# mbedXdotShield-V_1_2_0.net
KiCad netlist of a schematic drawn in EAGLE
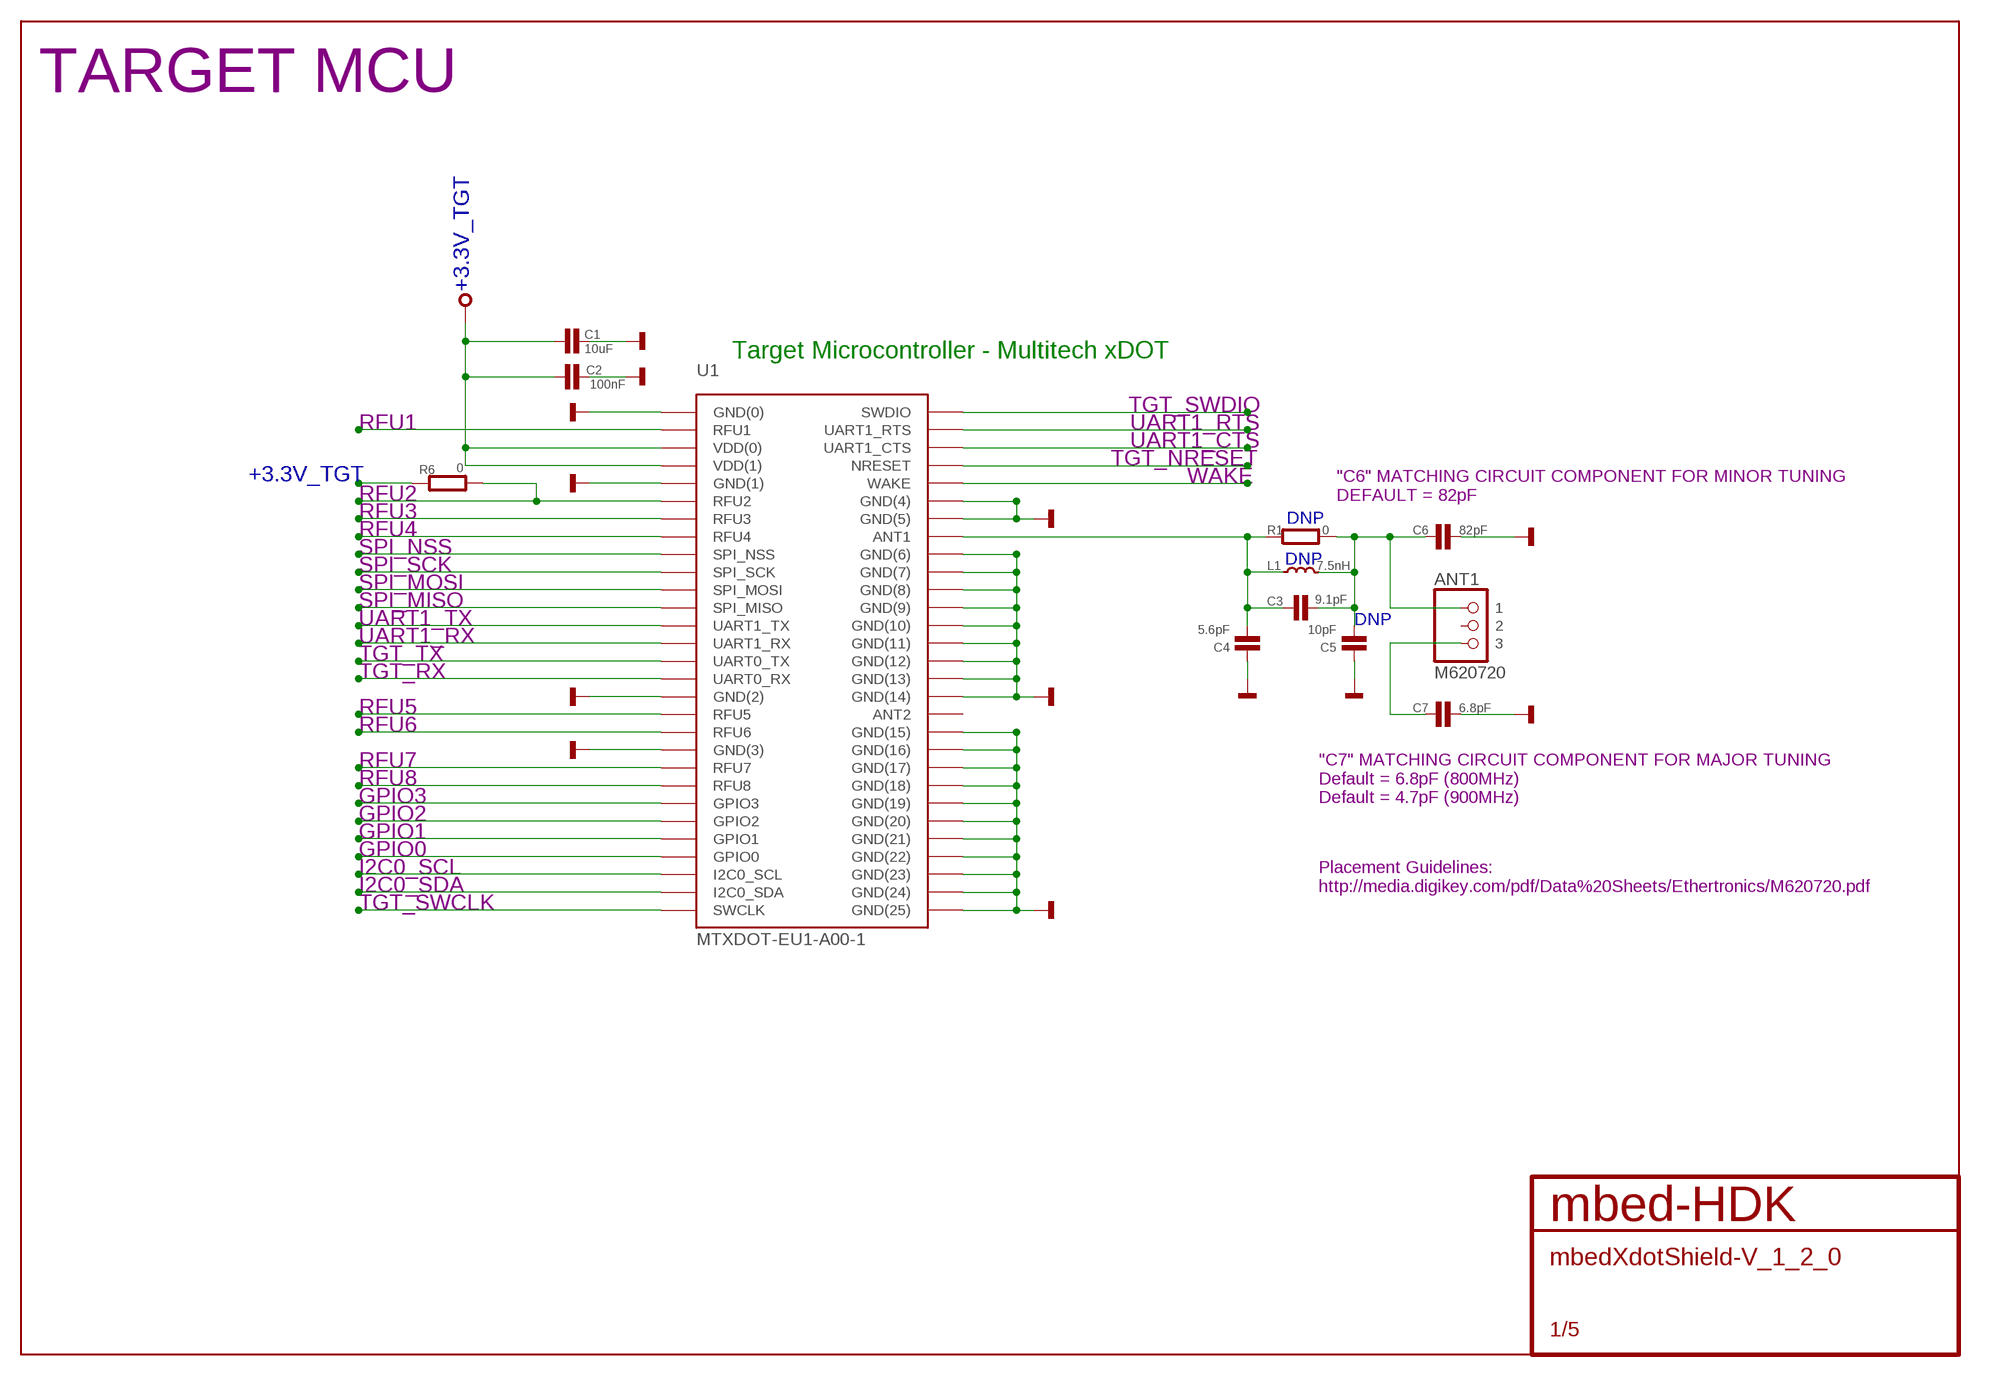
[diagram p0: schematic, sheet 1]
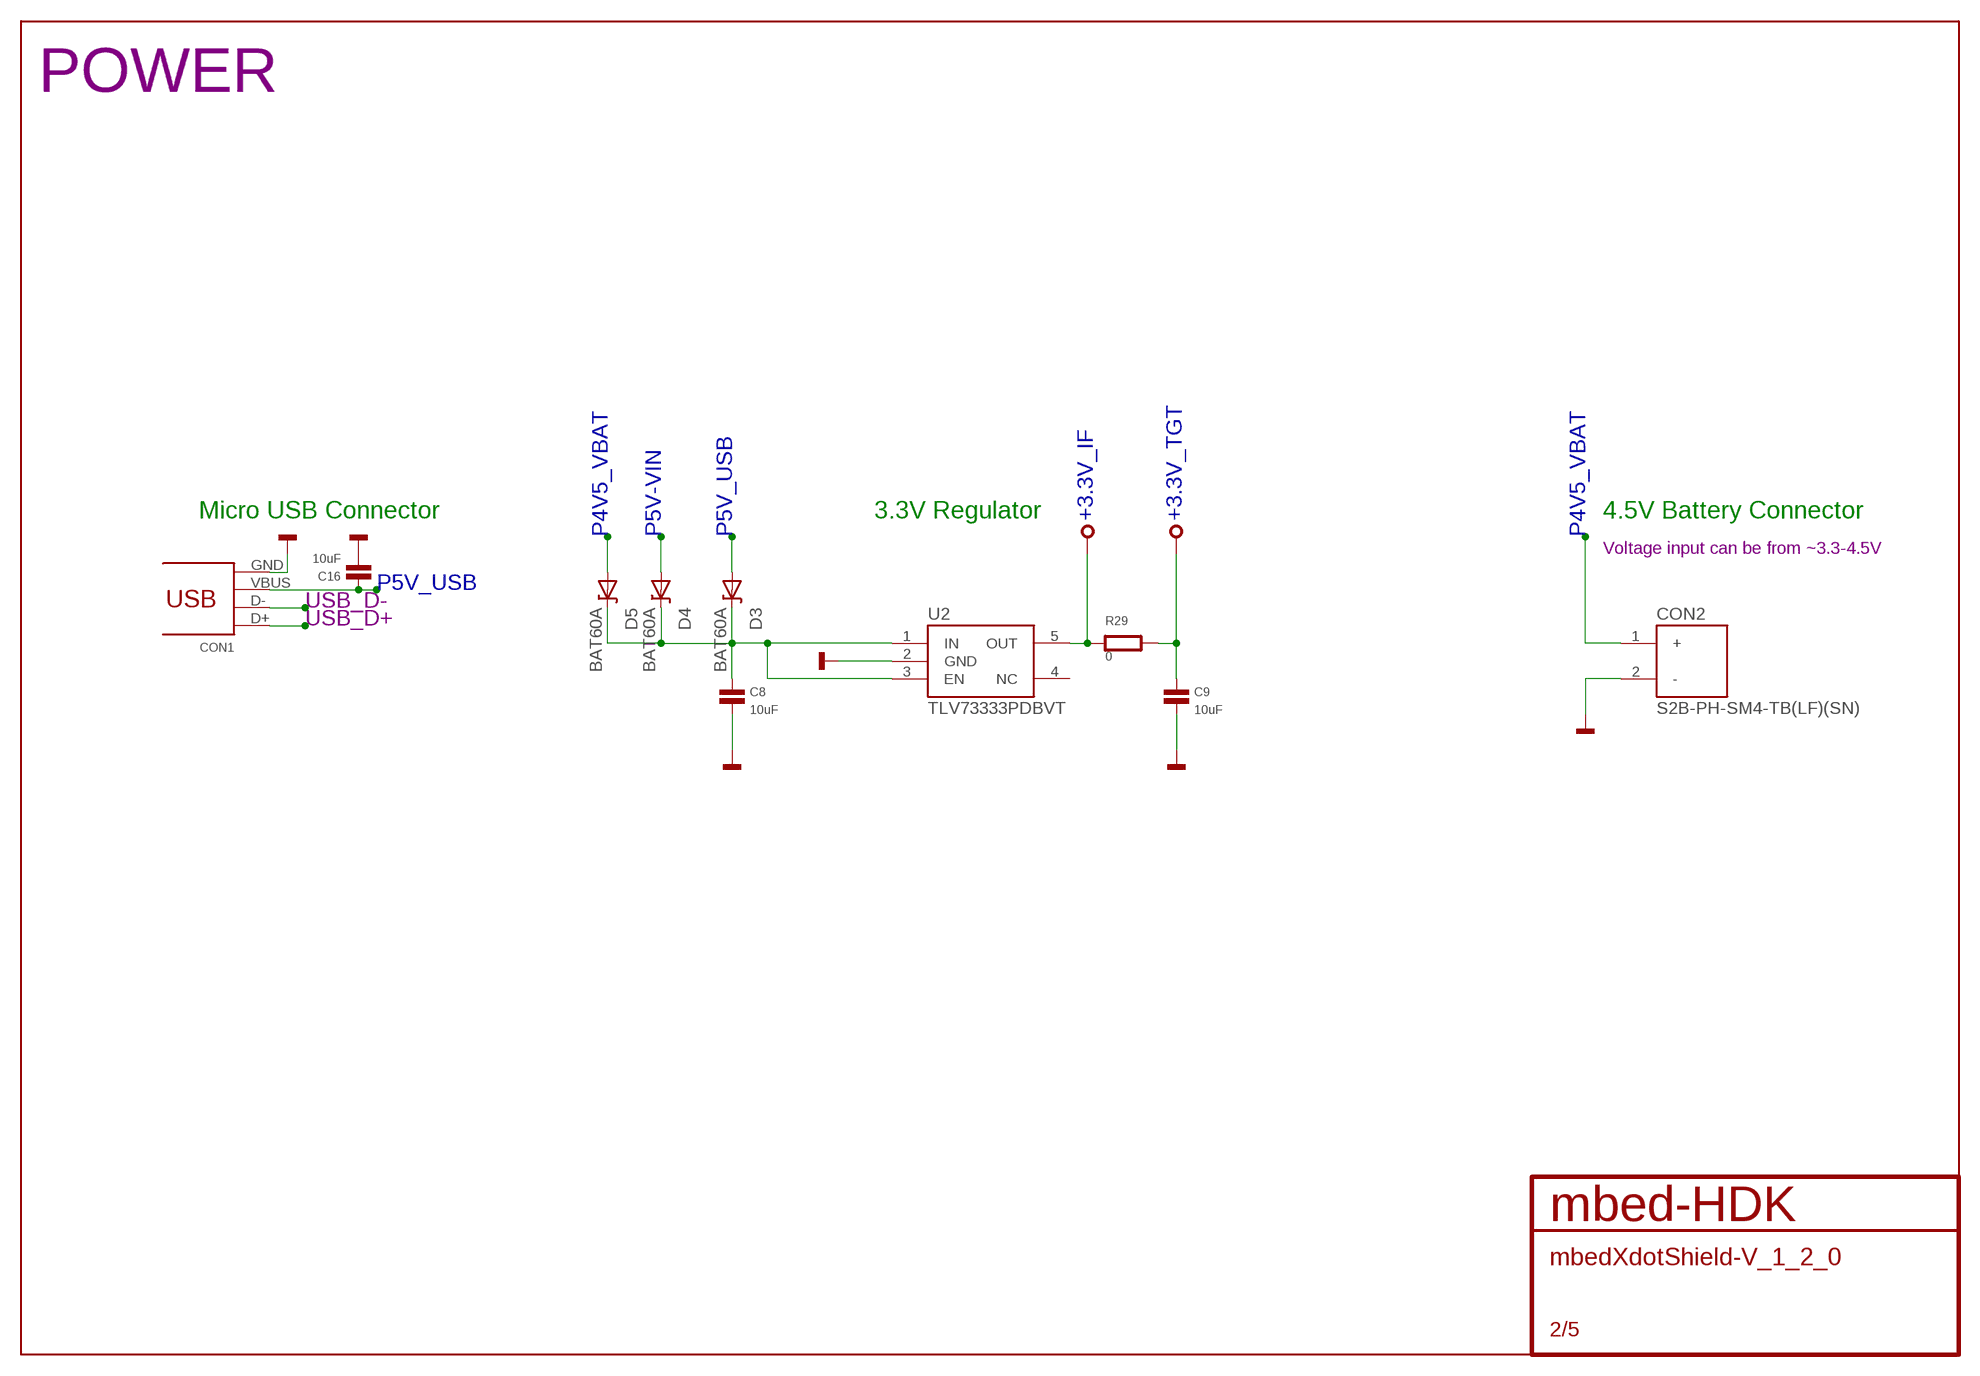
[diagram p1: schematic, sheet 2]
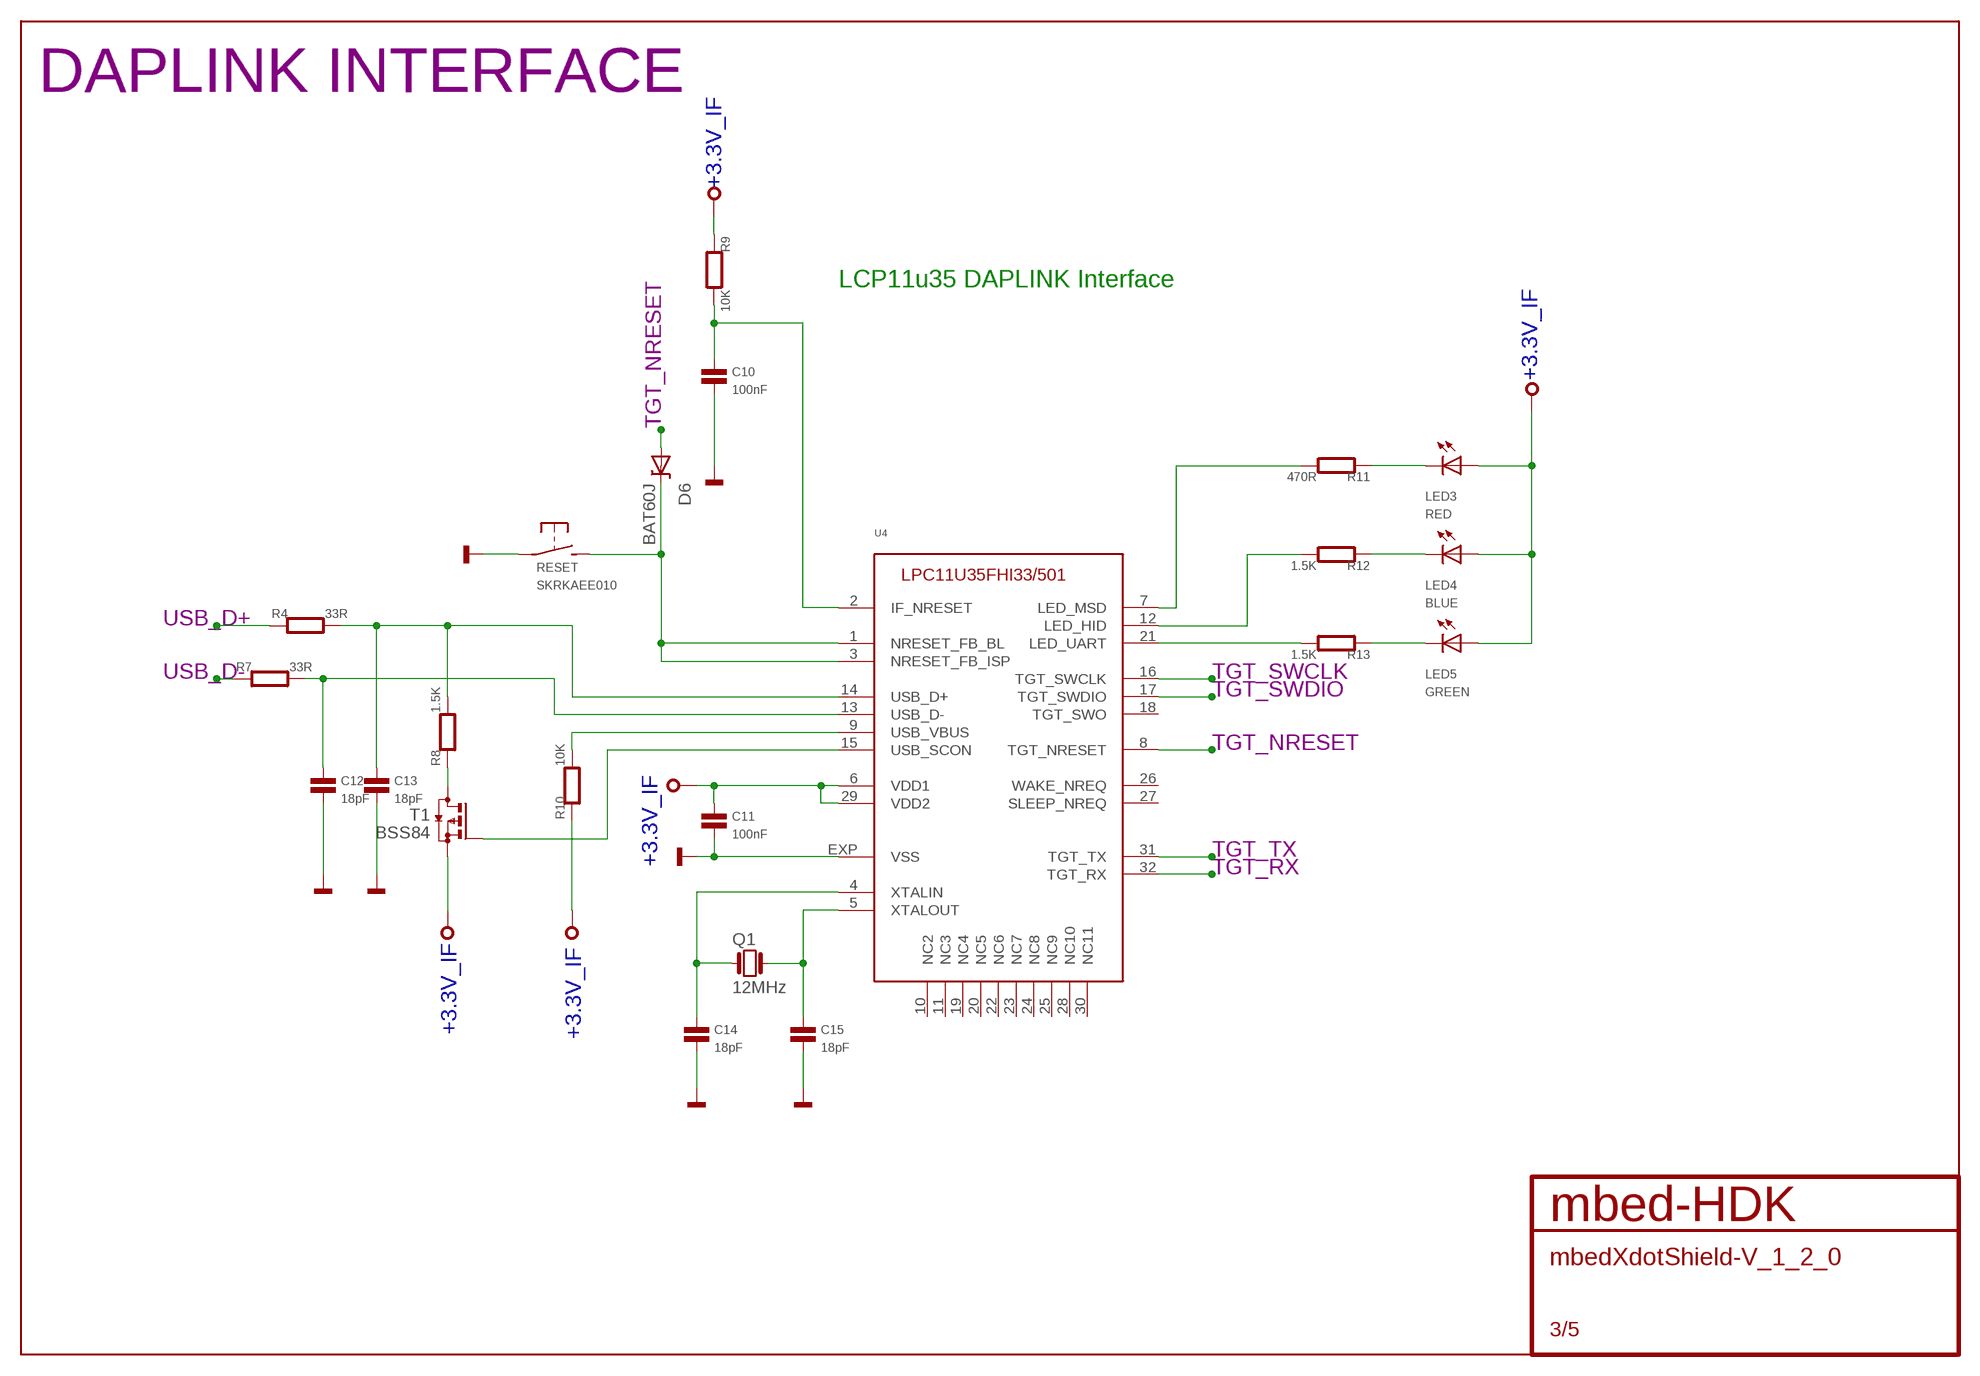
[diagram p2: schematic, sheet 3]
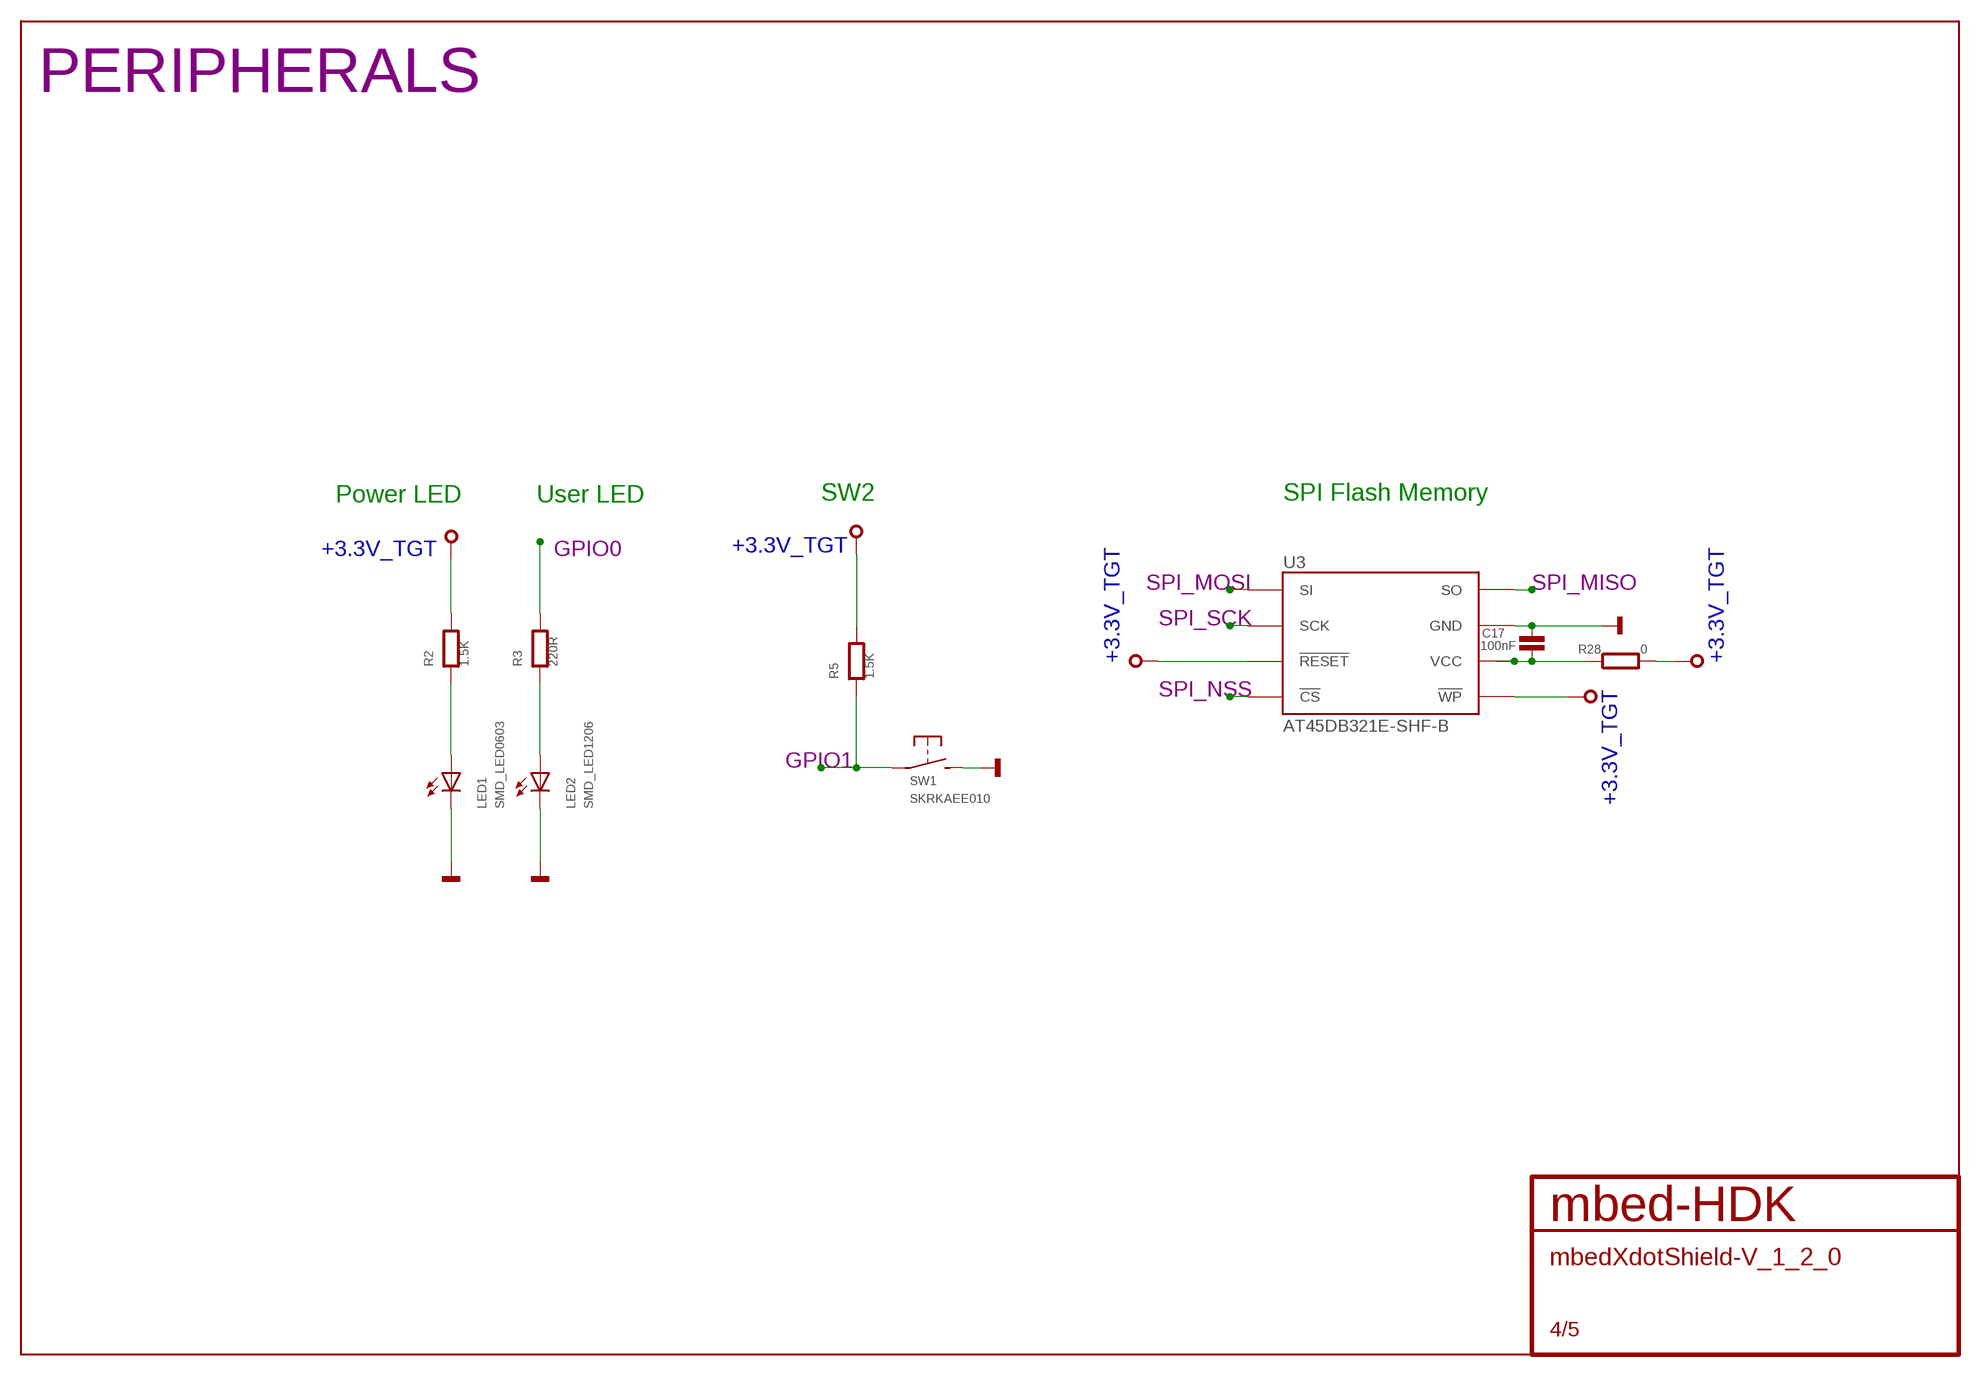
[diagram p3: schematic, sheet 4]
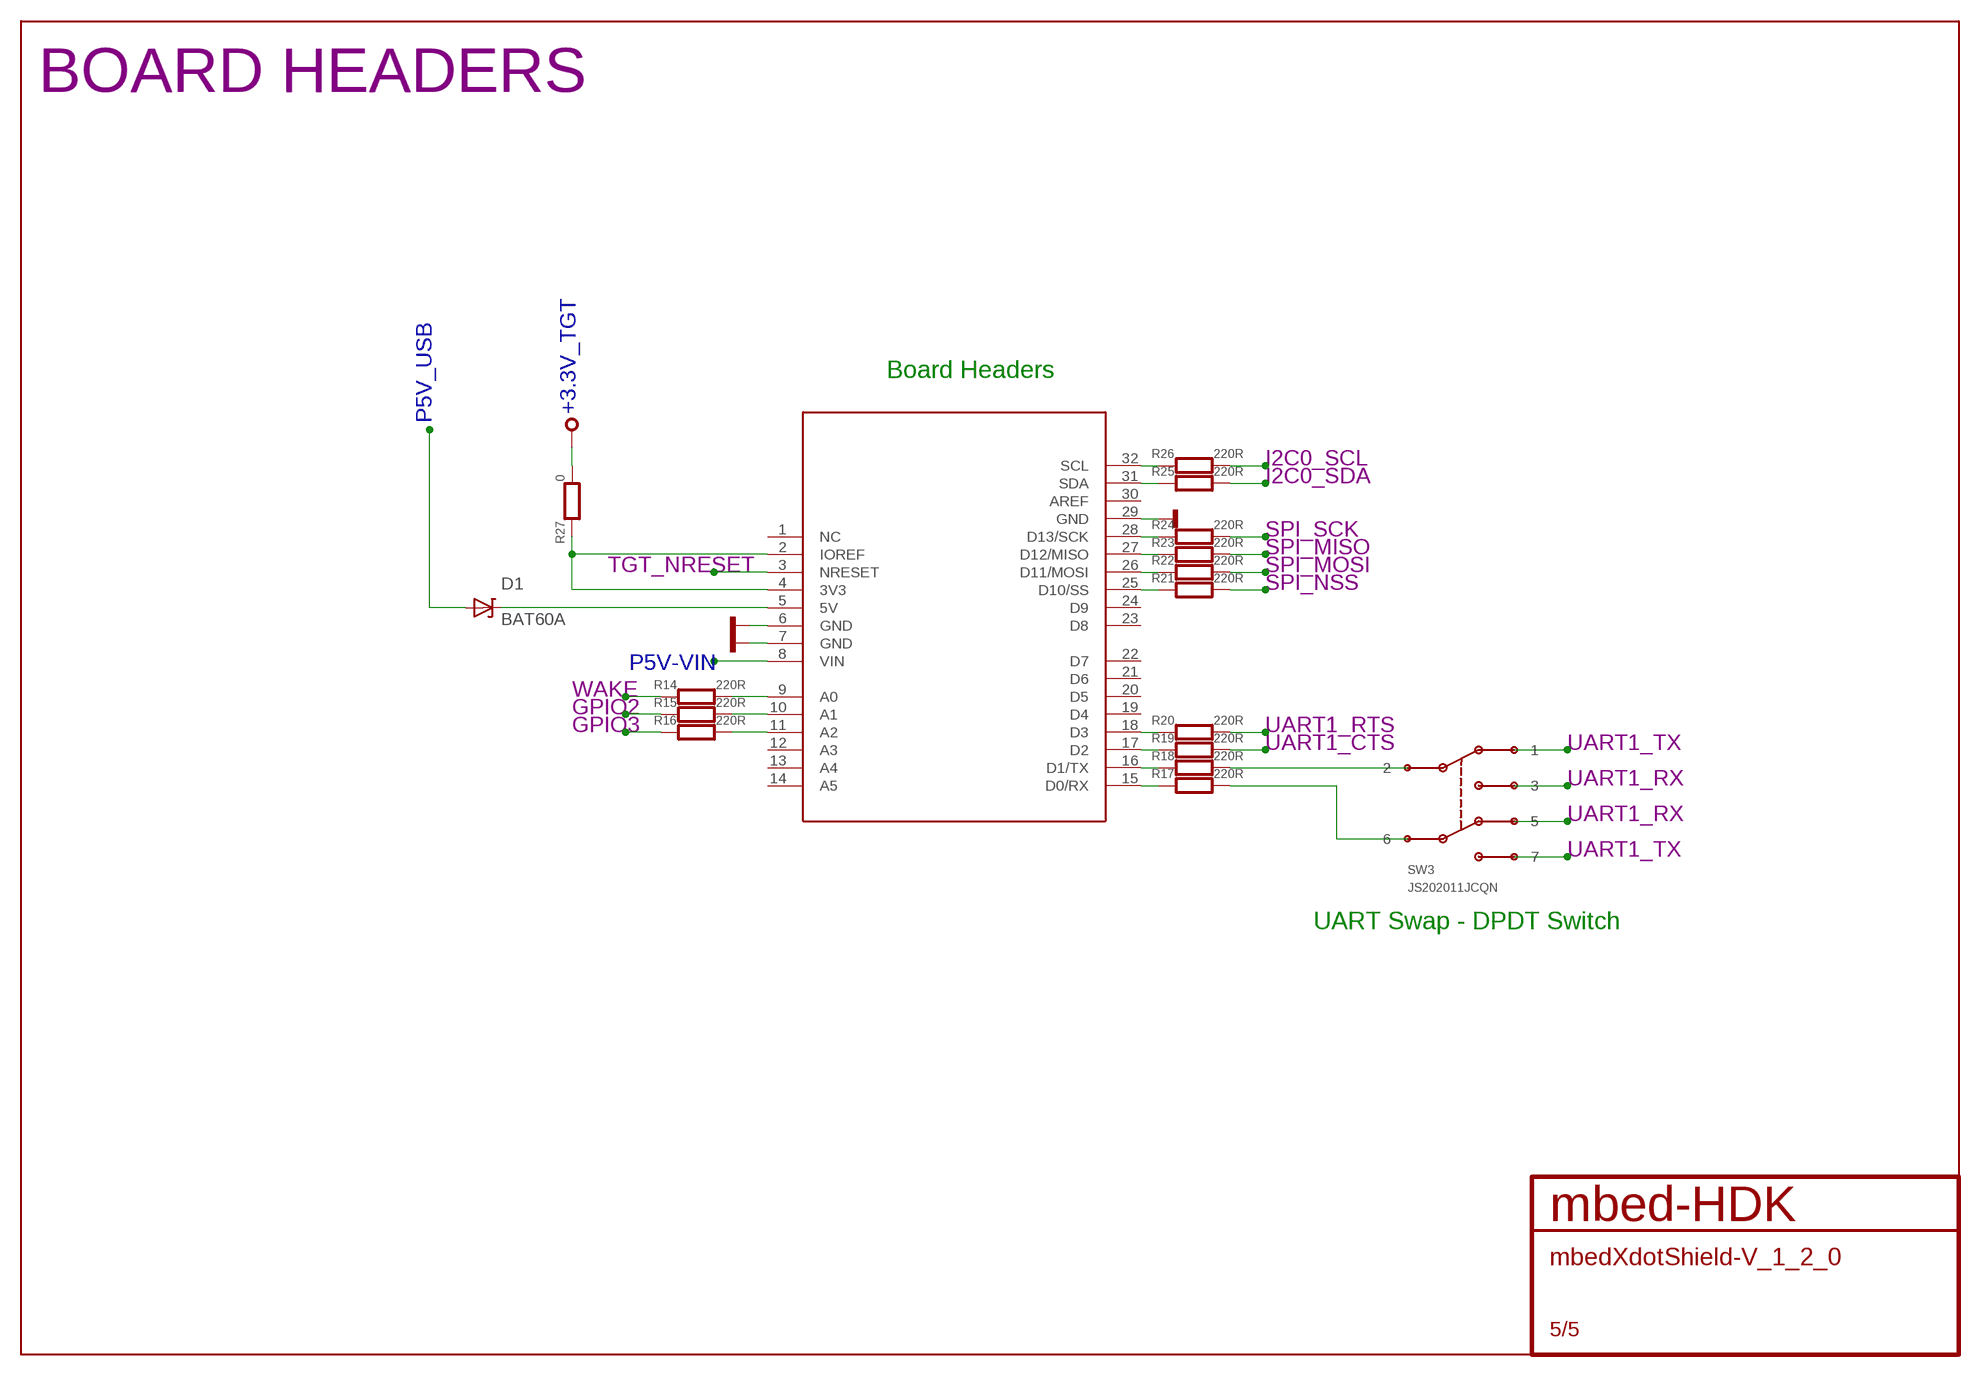
[diagram p4: schematic, sheet 5]

(export (version "E")
  (design (tool "Eeschema 10.0.6"))
  (components
    (comp (ref "BRD1")
      (value "K64F/K22F-SHIELD")
      (footprint "eagle-import:K64F_K22F")
      (libsource (lib "eagle-import") (part "K64F/K22F-SHIELD"))
    )
    (comp (ref "D1")
      (value "BAT60A")
      (footprint "eagle-import:SOD323")
      (fields (field (name "MF") "Infineon"))
      (libsource (lib "eagle-import") (part "BAT60A"))
    )
    (comp (ref "R14")
      (value "220R")
      (footprint "eagle-import:0402")
      (libsource (lib "eagle-import") (part "mbed-HDK-RLCQ_RESISTOR0402"))
    )
    (comp (ref "R15")
      (value "220R")
      (footprint "eagle-import:0402")
      (libsource (lib "eagle-import") (part "mbed-HDK-RLCQ_RESISTOR0402"))
    )
    (comp (ref "R16")
      (value "220R")
      (footprint "eagle-import:0402")
      (libsource (lib "eagle-import") (part "mbed-HDK-RLCQ_RESISTOR0402"))
    )
    (comp (ref "R17")
      (value "220R")
      (footprint "eagle-import:0402")
      (libsource (lib "eagle-import") (part "mbed-HDK-RLCQ_RESISTOR0402"))
    )
    (comp (ref "R18")
      (value "220R")
      (footprint "eagle-import:0402")
      (libsource (lib "eagle-import") (part "mbed-HDK-RLCQ_RESISTOR0402"))
    )
    (comp (ref "R19")
      (value "220R")
      (footprint "eagle-import:0402")
      (libsource (lib "eagle-import") (part "mbed-HDK-RLCQ_RESISTOR0402"))
    )
    (comp (ref "R20")
      (value "220R")
      (footprint "eagle-import:0402")
      (libsource (lib "eagle-import") (part "mbed-HDK-RLCQ_RESISTOR0402"))
    )
    (comp (ref "R21")
      (value "220R")
      (footprint "eagle-import:0402")
      (libsource (lib "eagle-import") (part "mbed-HDK-RLCQ_RESISTOR0402"))
    )
    (comp (ref "R22")
      (value "220R")
      (footprint "eagle-import:0402")
      (libsource (lib "eagle-import") (part "mbed-HDK-RLCQ_RESISTOR0402"))
    )
    (comp (ref "R23")
      (value "220R")
      (footprint "eagle-import:0402")
      (libsource (lib "eagle-import") (part "mbed-HDK-RLCQ_RESISTOR0402"))
    )
    (comp (ref "R24")
      (value "220R")
      (footprint "eagle-import:0402")
      (libsource (lib "eagle-import") (part "mbed-HDK-RLCQ_RESISTOR0402"))
    )
    (comp (ref "R25")
      (value "220R")
      (footprint "eagle-import:0402")
      (libsource (lib "eagle-import") (part "mbed-HDK-RLCQ_RESISTOR0402"))
    )
    (comp (ref "R26")
      (value "220R")
      (footprint "eagle-import:0402")
      (libsource (lib "eagle-import") (part "mbed-HDK-RLCQ_RESISTOR0402"))
    )
    (comp (ref "R27")
      (value "0")
      (footprint "eagle-import:0402")
      (libsource (lib "eagle-import") (part "mbed-HDK-RLCQ_RESISTOR0402"))
    )
    (comp (ref "SW3")
      (value "JS202011JCQN")
      (footprint "eagle-import:JS202011JCQN")
      (fields (field (name "MF") "C&K Components"))
      (libsource (lib "eagle-import") (part "JS202011JCQN"))
    )
    (comp (ref "C17")
      (value "100nF")
      (footprint "eagle-import:0603")
      (libsource (lib "eagle-import") (part "CAPACITOR0603"))
    )
    (comp (ref "LED1")
      (value "SMD_LED0603")
      (footprint "eagle-import:CHIPLED_0603")
      (fields (field (name "MF") "Wurth Electronics Inc"))
      (libsource (lib "eagle-import") (part "SMD_LED0603"))
    )
    (comp (ref "LED2")
      (value "SMD_LED1206")
      (footprint "eagle-import:CHIPLED_1206")
      (fields (field (name "MF") "Wurth Electronics Inc"))
      (libsource (lib "eagle-import") (part "SMD_LED1206"))
    )
    (comp (ref "R2")
      (value "1.5K")
      (footprint "eagle-import:0402")
      (libsource (lib "eagle-import") (part "mbed-HDK-RLCQ_RESISTOR0402"))
    )
    (comp (ref "R3")
      (value "220R")
      (footprint "eagle-import:0402")
      (libsource (lib "eagle-import") (part "mbed-HDK-RLCQ_RESISTOR0402"))
    )
    (comp (ref "R5")
      (value "1.5K")
      (footprint "eagle-import:0402")
      (libsource (lib "eagle-import") (part "mbed-HDK-RLCQ_RESISTOR0402"))
    )
    (comp (ref "R28")
      (value "0")
      (footprint "eagle-import:0402")
      (libsource (lib "eagle-import") (part "mbed-HDK-RLCQ_RESISTOR0402"))
    )
    (comp (ref "SW1")
      (value "SKRKAEE010")
      (footprint "eagle-import:SKRKAEE010")
      (fields (field (name "MF") "ALPS"))
      (libsource (lib "eagle-import") (part "SKRKAEE010"))
    )
    (comp (ref "U3")
      (value "AT45DB321E-SHF-B")
      (footprint "eagle-import:SO8")
      (fields (field (name "MF") "Adesto Technologies"))
      (libsource (lib "eagle-import") (part "AT45DB321E-SHF-B"))
    )
    (comp (ref "ANT1")
      (value "M620720")
      (footprint "eagle-import:M620720")
      (fields (field (name "MF") "Ethertronics"))
      (libsource (lib "eagle-import") (part "M620720"))
    )
    (comp (ref "C1")
      (value "10uF")
      (footprint "eagle-import:0603")
      (libsource (lib "eagle-import") (part "CAPACITOR0603"))
    )
    (comp (ref "C2")
      (value "100nF")
      (footprint "eagle-import:0603")
      (libsource (lib "eagle-import") (part "CAPACITOR0603"))
    )
    (comp (ref "C3")
      (value "9.1pF")
      (footprint "eagle-import:0402")
      (libsource (lib "eagle-import") (part "CAPACITOR0402"))
    )
    (comp (ref "C4")
      (value "5.6pF")
      (footprint "eagle-import:0402")
      (libsource (lib "eagle-import") (part "CAPACITOR0402"))
    )
    (comp (ref "C5")
      (value "10pF")
      (footprint "eagle-import:0402")
      (libsource (lib "eagle-import") (part "CAPACITOR0402"))
    )
    (comp (ref "C6")
      (value "82pF")
      (footprint "eagle-import:0402")
      (libsource (lib "eagle-import") (part "CAPACITOR0402"))
    )
    (comp (ref "C7")
      (value "6.8pF")
      (footprint "eagle-import:0402")
      (libsource (lib "eagle-import") (part "CAPACITOR0402"))
    )
    (comp (ref "L1")
      (value "7.5nH")
      (footprint "eagle-import:0402")
      (libsource (lib "eagle-import") (part "INDUCTOR0402"))
    )
    (comp (ref "R1")
      (value "0")
      (footprint "eagle-import:0402")
      (libsource (lib "eagle-import") (part "mbed-HDK-RLCQ_RESISTOR0402"))
    )
    (comp (ref "R6")
      (value "0")
      (footprint "eagle-import:0402")
      (libsource (lib "eagle-import") (part "mbed-HDK-RLCQ_RESISTOR0402"))
    )
    (comp (ref "U1")
      (value "MTXDOT-EU1-A00-1")
      (footprint "eagle-import:MTXDOT-EU1_NA1-A00-1")
      (fields (field (name "MF") "Multi-Tech Systems Inc."))
      (libsource (lib "eagle-import") (part "MTXDOT-EU1-A00-1"))
    )
    (comp (ref "C10")
      (value "100nF")
      (footprint "eagle-import:0402")
      (libsource (lib "eagle-import") (part "CAPACITOR0402"))
    )
    (comp (ref "C11")
      (value "100nF")
      (footprint "eagle-import:0402")
      (libsource (lib "eagle-import") (part "CAPACITOR0402"))
    )
    (comp (ref "C12")
      (value "18pF")
      (footprint "eagle-import:0402")
      (libsource (lib "eagle-import") (part "CAPACITOR0402"))
    )
    (comp (ref "C13")
      (value "18pF")
      (footprint "eagle-import:0402")
      (libsource (lib "eagle-import") (part "CAPACITOR0402"))
    )
    (comp (ref "C14")
      (value "18pF")
      (footprint "eagle-import:0402")
      (libsource (lib "eagle-import") (part "CAPACITOR0402"))
    )
    (comp (ref "C15")
      (value "18pF")
      (footprint "eagle-import:0402")
      (libsource (lib "eagle-import") (part "CAPACITOR0402"))
    )
    (comp (ref "D6")
      (value "BAT60J")
      (footprint "eagle-import:SOD323")
      (fields (field (name "MF") "STMicroelectronics"))
      (libsource (lib "eagle-import") (part "BAT60J"))
    )
    (comp (ref "LED3")
      (value "RED")
      (footprint "eagle-import:CHIPLED_0603")
      (fields (field (name "MF") "Wurth Electronics Inc"))
      (libsource (lib "eagle-import") (part "SMD_LED0603"))
    )
    (comp (ref "LED4")
      (value "BLUE")
      (footprint "eagle-import:CHIPLED_0603")
      (fields (field (name "MF") "Wurth Electronics Inc"))
      (libsource (lib "eagle-import") (part "SMD_LED0603"))
    )
    (comp (ref "LED5")
      (value "GREEN")
      (footprint "eagle-import:CHIPLED_0603")
      (fields (field (name "MF") "Wurth Electronics Inc"))
      (libsource (lib "eagle-import") (part "SMD_LED0603"))
    )
    (comp (ref "Q1")
      (value "12MHz")
      (footprint "eagle-import:3.2X.2.5")
      (libsource (lib "eagle-import") (part "Q_3.2X2.5"))
    )
    (comp (ref "R4")
      (value "33R")
      (footprint "eagle-import:0402")
      (libsource (lib "eagle-import") (part "mbed-HDK-RLCQ_RESISTOR0402"))
    )
    (comp (ref "R7")
      (value "33R")
      (footprint "eagle-import:0402")
      (libsource (lib "eagle-import") (part "mbed-HDK-RLCQ_RESISTOR0402"))
    )
    (comp (ref "R8")
      (value "1.5K")
      (footprint "eagle-import:0402")
      (libsource (lib "eagle-import") (part "mbed-HDK-RLCQ_RESISTOR0402"))
    )
    (comp (ref "R9")
      (value "10K")
      (footprint "eagle-import:0402")
      (libsource (lib "eagle-import") (part "mbed-HDK-RLCQ_RESISTOR0402"))
    )
    (comp (ref "R10")
      (value "10K")
      (footprint "eagle-import:0402")
      (libsource (lib "eagle-import") (part "mbed-HDK-RLCQ_RESISTOR0402"))
    )
    (comp (ref "R11")
      (value "470R")
      (footprint "eagle-import:0402")
      (libsource (lib "eagle-import") (part "mbed-HDK-RLCQ_RESISTOR0402"))
    )
    (comp (ref "R12")
      (value "1.5K")
      (footprint "eagle-import:0402")
      (libsource (lib "eagle-import") (part "mbed-HDK-RLCQ_RESISTOR0402"))
    )
    (comp (ref "R13")
      (value "1.5K")
      (footprint "eagle-import:0402")
      (libsource (lib "eagle-import") (part "mbed-HDK-RLCQ_RESISTOR0402"))
    )
    (comp (ref "RESET")
      (value "SKRKAEE010")
      (footprint "eagle-import:SKRKAEE010")
      (fields (field (name "MF") "ALPS"))
      (libsource (lib "eagle-import") (part "SKRKAEE010"))
    )
    (comp (ref "T1")
      (value "BSS84")
      (footprint "eagle-import:SOT23-3")
      (fields (field (name "MF") "Fairchild Semiconductor"))
      (libsource (lib "eagle-import") (part "BSS84"))
    )
    (comp (ref "U4")
      (value "IF-LPC11U35")
      (footprint "eagle-import:HVQFN33")
      (libsource (lib "eagle-import") (part "IF-LPC11U35"))
    )
    (comp (ref "C8")
      (value "10uF")
      (footprint "eagle-import:0603")
      (libsource (lib "eagle-import") (part "CAPACITOR0603"))
    )
    (comp (ref "C9")
      (value "10uF")
      (footprint "eagle-import:0603")
      (libsource (lib "eagle-import") (part "CAPACITOR0603"))
    )
    (comp (ref "C16")
      (value "10uF")
      (footprint "eagle-import:0603")
      (libsource (lib "eagle-import") (part "CAPACITOR0603"))
    )
    (comp (ref "CON1")
      (value "47346-0001")
      (footprint "eagle-import:USB-MICRO-B-H")
      (fields (field (name "MF") "MOLEX"))
      (libsource (lib "eagle-import") (part "47346-0001"))
    )
    (comp (ref "CON2")
      (value "S2B-PH-SM4-TB(LF)(SN)")
      (footprint "eagle-import:S2B-PH-SM4-TB(LF)(SN)")
      (fields (field (name "MF") "JST"))
      (libsource (lib "eagle-import") (part "S2B-PH-SM4-TB(LF)(SN)"))
    )
    (comp (ref "D3")
      (value "BAT60A")
      (footprint "eagle-import:SOD323")
      (fields (field (name "MF") "Infineon"))
      (libsource (lib "eagle-import") (part "BAT60A"))
    )
    (comp (ref "D4")
      (value "BAT60A")
      (footprint "eagle-import:SOD323")
      (fields (field (name "MF") "Infineon"))
      (libsource (lib "eagle-import") (part "BAT60A"))
    )
    (comp (ref "D5")
      (value "BAT60A")
      (footprint "eagle-import:SOD323")
      (fields (field (name "MF") "Infineon"))
      (libsource (lib "eagle-import") (part "BAT60A"))
    )
    (comp (ref "R29")
      (value "0")
      (footprint "eagle-import:0805")
      (libsource (lib "eagle-import") (part "RESISTOR0805"))
    )
    (comp (ref "U2")
      (value "TLV73333PDBVT")
      (footprint "eagle-import:SOT23-5")
      (fields (field (name "MF") "Texas Instruments"))
      (libsource (lib "eagle-import") (part "TLV73333PDBVT"))
    )
  )
  (nets
    (net (code "1") (name "+3.3V_IF") (class "Default")
      (node (ref "C11") (pin "1") (pinfunction "P$1_1") (pintype "passive"))
      (node (ref "LED3") (pin "A") (pinfunction "A_A") (pintype "passive"))
      (node (ref "LED4") (pin "A") (pinfunction "A_A") (pintype "passive"))
      (node (ref "LED5") (pin "A") (pinfunction "A_A") (pintype "passive"))
      (node (ref "R10") (pin "1") (pinfunction "P$1_1") (pintype "passive"))
      (node (ref "R29") (pin "1") (pinfunction "P$1_1") (pintype "passive"))
      (node (ref "R9") (pin "1") (pinfunction "P$1_1") (pintype "passive"))
      (node (ref "T1") (pin "2") (pinfunction "S_2") (pintype "passive"))
      (node (ref "U2") (pin "5") (pinfunction "OUT_5") (pintype "bidirectional"))
      (node (ref "U4") (pin "29") (pinfunction "VDD2_29") (pintype "bidirectional"))
      (node (ref "U4") (pin "6") (pinfunction "VDD1_6") (pintype "bidirectional"))
    )
    (net (code "2") (name "+3.3V_TGT") (class "Default")
      (node (ref "C1") (pin "1") (pinfunction "P$1_1") (pintype "passive"))
      (node (ref "C2") (pin "1") (pinfunction "P$1_1") (pintype "passive"))
      (node (ref "C9") (pin "1") (pinfunction "P$1_1") (pintype "passive"))
      (node (ref "R2") (pin "2") (pinfunction "P$2_2") (pintype "passive"))
      (node (ref "R27") (pin "2") (pinfunction "P$2_2") (pintype "passive"))
      (node (ref "R28") (pin "2") (pinfunction "P$2_2") (pintype "passive"))
      (node (ref "R29") (pin "2") (pinfunction "P$2_2") (pintype "passive"))
      (node (ref "R5") (pin "2") (pinfunction "P$2_2") (pintype "passive"))
      (node (ref "R6") (pin "1") (pinfunction "P$1_1") (pintype "passive"))
      (node (ref "U1") (pin "P$3") (pinfunction "VDD(0)_P$3") (pintype "bidirectional"))
      (node (ref "U1") (pin "P$4") (pinfunction "VDD(1)_P$4") (pintype "bidirectional"))
      (node (ref "U3") (pin "3") (pinfunction "~{RESET}_3") (pintype "bidirectional"))
      (node (ref "U3") (pin "5") (pinfunction "~{WP}_5") (pintype "bidirectional"))
    )
    (net (code "3") (name "GND") (class "Default")
      (node (ref "BRD1") (pin "29") (pinfunction "GND_29") (pintype "bidirectional"))
      (node (ref "BRD1") (pin "6") (pinfunction "GND_6") (pintype "bidirectional"))
      (node (ref "BRD1") (pin "7") (pinfunction "GND_7") (pintype "bidirectional"))
      (node (ref "C1") (pin "2") (pinfunction "P$2_2") (pintype "passive"))
      (node (ref "C10") (pin "2") (pinfunction "P$2_2") (pintype "passive"))
      (node (ref "C11") (pin "2") (pinfunction "P$2_2") (pintype "passive"))
      (node (ref "C12") (pin "2") (pinfunction "P$2_2") (pintype "passive"))
      (node (ref "C13") (pin "2") (pinfunction "P$2_2") (pintype "passive"))
      (node (ref "C14") (pin "2") (pinfunction "P$2_2") (pintype "passive"))
      (node (ref "C15") (pin "2") (pinfunction "P$2_2") (pintype "passive"))
      (node (ref "C16") (pin "2") (pinfunction "P$2_2") (pintype "passive"))
      (node (ref "C17") (pin "1") (pinfunction "P$1_1") (pintype "passive"))
      (node (ref "C2") (pin "2") (pinfunction "P$2_2") (pintype "passive"))
      (node (ref "C4") (pin "1") (pinfunction "P$1_1") (pintype "passive"))
      (node (ref "C5") (pin "1") (pinfunction "P$1_1") (pintype "passive"))
      (node (ref "C6") (pin "1") (pinfunction "P$1_1") (pintype "passive"))
      (node (ref "C7") (pin "1") (pinfunction "P$1_1") (pintype "passive"))
      (node (ref "C8") (pin "2") (pinfunction "P$2_2") (pintype "passive"))
      (node (ref "C9") (pin "2") (pinfunction "P$2_2") (pintype "passive"))
      (node (ref "CON1") (pin "GND") (pinfunction "GND_GND") (pintype "bidirectional"))
      (node (ref "CON2") (pin "2") (pinfunction "-_2") (pintype "bidirectional"))
      (node (ref "LED1") (pin "C") (pinfunction "C_C") (pintype "passive"))
      (node (ref "LED2") (pin "C") (pinfunction "C_C") (pintype "passive"))
      (node (ref "RESET") (pin "P$1") (pinfunction "P_P$1") (pintype "passive"))
      (node (ref "SW1") (pin "P$2") (pinfunction "S_P$2") (pintype "passive"))
      (node (ref "U1") (pin "P$1") (pinfunction "GND(0)_P$1") (pintype "bidirectional"))
      (node (ref "U1") (pin "P$17") (pinfunction "GND(2)_P$17") (pintype "bidirectional"))
      (node (ref "U1") (pin "P$20") (pinfunction "GND(3)_P$20") (pintype "bidirectional"))
      (node (ref "U1") (pin "P$35") (pinfunction "GND(4)_P$35") (pintype "bidirectional"))
      (node (ref "U1") (pin "P$36") (pinfunction "GND(5)_P$36") (pintype "bidirectional"))
      (node (ref "U1") (pin "P$38") (pinfunction "GND(6)_P$38") (pintype "bidirectional"))
      (node (ref "U1") (pin "P$39") (pinfunction "GND(7)_P$39") (pintype "bidirectional"))
      (node (ref "U1") (pin "P$40") (pinfunction "GND(8)_P$40") (pintype "bidirectional"))
      (node (ref "U1") (pin "P$41") (pinfunction "GND(9)_P$41") (pintype "bidirectional"))
      (node (ref "U1") (pin "P$42") (pinfunction "GND(10)_P$42") (pintype "bidirectional"))
      (node (ref "U1") (pin "P$43") (pinfunction "GND(11)_P$43") (pintype "bidirectional"))
      (node (ref "U1") (pin "P$44") (pinfunction "GND(12)_P$44") (pintype "bidirectional"))
      (node (ref "U1") (pin "P$45") (pinfunction "GND(13)_P$45") (pintype "bidirectional"))
      (node (ref "U1") (pin "P$46") (pinfunction "GND(14)_P$46") (pintype "bidirectional"))
      (node (ref "U1") (pin "P$48") (pinfunction "GND(15)_P$48") (pintype "bidirectional"))
      (node (ref "U1") (pin "P$49") (pinfunction "GND(16)_P$49") (pintype "bidirectional"))
      (node (ref "U1") (pin "P$5") (pinfunction "GND(1)_P$5") (pintype "bidirectional"))
      (node (ref "U1") (pin "P$50") (pinfunction "GND(17)_P$50") (pintype "bidirectional"))
      (node (ref "U1") (pin "P$51") (pinfunction "GND(18)_P$51") (pintype "bidirectional"))
      (node (ref "U1") (pin "P$52") (pinfunction "GND(19)_P$52") (pintype "bidirectional"))
      (node (ref "U1") (pin "P$53") (pinfunction "GND(20)_P$53") (pintype "bidirectional"))
      (node (ref "U1") (pin "P$54") (pinfunction "GND(21)_P$54") (pintype "bidirectional"))
      (node (ref "U1") (pin "P$55") (pinfunction "GND(22)_P$55") (pintype "bidirectional"))
      (node (ref "U1") (pin "P$56") (pinfunction "GND(23)_P$56") (pintype "bidirectional"))
      (node (ref "U1") (pin "P$57") (pinfunction "GND(24)_P$57") (pintype "bidirectional"))
      (node (ref "U1") (pin "P$58") (pinfunction "GND(25)_P$58") (pintype "bidirectional"))
      (node (ref "U2") (pin "2") (pinfunction "GND_2") (pintype "bidirectional"))
      (node (ref "U3") (pin "7") (pinfunction "GND_7") (pintype "bidirectional"))
      (node (ref "U4") (pin "EXP") (pinfunction "VSS_EXP") (pintype "bidirectional"))
    )
    (net (code "4") (name "GPIO0") (class "Default")
      (node (ref "R3") (pin "2") (pinfunction "P$2_2") (pintype "passive"))
      (node (ref "U1") (pin "P$26") (pinfunction "GPIO0_P$26") (pintype "bidirectional"))
    )
    (net (code "5") (name "GPIO1") (class "Default")
      (node (ref "R5") (pin "1") (pinfunction "P$1_1") (pintype "passive"))
      (node (ref "SW1") (pin "P$1") (pinfunction "P_P$1") (pintype "passive"))
      (node (ref "U1") (pin "P$25") (pinfunction "GPIO1_P$25") (pintype "bidirectional"))
    )
    (net (code "6") (name "GPIO2") (class "Default")
      (node (ref "R15") (pin "1") (pinfunction "P$1_1") (pintype "passive"))
      (node (ref "U1") (pin "P$24") (pinfunction "GPIO2_P$24") (pintype "bidirectional"))
    )
    (net (code "7") (name "GPIO3") (class "Default")
      (node (ref "R16") (pin "1") (pinfunction "P$1_1") (pintype "passive"))
      (node (ref "U1") (pin "P$23") (pinfunction "GPIO3_P$23") (pintype "bidirectional"))
    )
    (net (code "8") (name "I2C0_SCL") (class "Default")
      (node (ref "R26") (pin "2") (pinfunction "P$2_2") (pintype "passive"))
      (node (ref "U1") (pin "P$27") (pinfunction "I2C0_SCL_P$27") (pintype "bidirectional"))
    )
    (net (code "9") (name "I2C0_SDA") (class "Default")
      (node (ref "R25") (pin "2") (pinfunction "P$2_2") (pintype "passive"))
      (node (ref "U1") (pin "P$28") (pinfunction "I2C0_SDA_P$28") (pintype "bidirectional"))
    )
    (net (code "10") (name "Net-(ANT1-1)") (class "Default")
      (node (ref "ANT1") (pin "P$1") (pinfunction "1_P$1") (pintype "passive"))
      (node (ref "C3") (pin "2") (pinfunction "P$2_2") (pintype "passive"))
      (node (ref "C5") (pin "2") (pinfunction "P$2_2") (pintype "passive"))
      (node (ref "C6") (pin "2") (pinfunction "P$2_2") (pintype "passive"))
      (node (ref "L1") (pin "2") (pinfunction "P$2_2") (pintype "bidirectional"))
      (node (ref "R1") (pin "2") (pinfunction "P$2_2") (pintype "passive"))
    )
    (net (code "11") (name "Net-(ANT1-3)") (class "Default")
      (node (ref "ANT1") (pin "P$3") (pinfunction "3_P$3") (pintype "passive"))
      (node (ref "C7") (pin "2") (pinfunction "P$2_2") (pintype "passive"))
    )
    (net (code "12") (name "Net-(BRD1-3V3)") (class "Default")
      (node (ref "BRD1") (pin "2") (pinfunction "IOREF_2") (pintype "bidirectional"))
      (node (ref "BRD1") (pin "4") (pinfunction "3V3_4") (pintype "bidirectional"))
      (node (ref "R27") (pin "1") (pinfunction "P$1_1") (pintype "passive"))
    )
    (net (code "13") (name "Net-(BRD1-5V)") (class "Default")
      (node (ref "BRD1") (pin "5") (pinfunction "5V_5") (pintype "bidirectional"))
      (node (ref "D1") (pin "K") (pinfunction "K_K") (pintype "passive"))
    )
    (net (code "14") (name "Net-(BRD1-A0)") (class "Default")
      (node (ref "BRD1") (pin "9") (pinfunction "A0_9") (pintype "bidirectional"))
      (node (ref "R14") (pin "2") (pinfunction "P$2_2") (pintype "passive"))
    )
    (net (code "15") (name "Net-(BRD1-A1)") (class "Default")
      (node (ref "BRD1") (pin "10") (pinfunction "A1_10") (pintype "bidirectional"))
      (node (ref "R15") (pin "2") (pinfunction "P$2_2") (pintype "passive"))
    )
    (net (code "16") (name "Net-(BRD1-A2)") (class "Default")
      (node (ref "BRD1") (pin "11") (pinfunction "A2_11") (pintype "bidirectional"))
      (node (ref "R16") (pin "2") (pinfunction "P$2_2") (pintype "passive"))
    )
    (net (code "17") (name "Net-(BRD1-D0{slash}RX)") (class "Default")
      (node (ref "BRD1") (pin "15") (pinfunction "D0/RX_15") (pintype "bidirectional"))
      (node (ref "R17") (pin "1") (pinfunction "P$1_1") (pintype "passive"))
    )
    (net (code "18") (name "Net-(BRD1-D1{slash}TX)") (class "Default")
      (node (ref "BRD1") (pin "16") (pinfunction "D1/TX_16") (pintype "bidirectional"))
      (node (ref "R18") (pin "1") (pinfunction "P$1_1") (pintype "passive"))
    )
    (net (code "19") (name "Net-(BRD1-D2)") (class "Default")
      (node (ref "BRD1") (pin "17") (pinfunction "D2_17") (pintype "bidirectional"))
      (node (ref "R19") (pin "1") (pinfunction "P$1_1") (pintype "passive"))
    )
    (net (code "20") (name "Net-(BRD1-D3)") (class "Default")
      (node (ref "BRD1") (pin "18") (pinfunction "D3_18") (pintype "bidirectional"))
      (node (ref "R20") (pin "1") (pinfunction "P$1_1") (pintype "passive"))
    )
    (net (code "21") (name "Net-(BRD1-D10{slash}SS)") (class "Default")
      (node (ref "BRD1") (pin "25") (pinfunction "D10/SS_25") (pintype "bidirectional"))
      (node (ref "R21") (pin "1") (pinfunction "P$1_1") (pintype "passive"))
    )
    (net (code "22") (name "Net-(BRD1-D11{slash}MOSI)") (class "Default")
      (node (ref "BRD1") (pin "26") (pinfunction "D11/MOSI_26") (pintype "bidirectional"))
      (node (ref "R22") (pin "1") (pinfunction "P$1_1") (pintype "passive"))
    )
    (net (code "23") (name "Net-(BRD1-D12{slash}MISO)") (class "Default")
      (node (ref "BRD1") (pin "27") (pinfunction "D12/MISO_27") (pintype "bidirectional"))
      (node (ref "R23") (pin "1") (pinfunction "P$1_1") (pintype "passive"))
    )
    (net (code "24") (name "Net-(BRD1-D13{slash}SCK)") (class "Default")
      (node (ref "BRD1") (pin "28") (pinfunction "D13/SCK_28") (pintype "bidirectional"))
      (node (ref "R24") (pin "1") (pinfunction "P$1_1") (pintype "passive"))
    )
    (net (code "25") (name "Net-(BRD1-SCL)") (class "Default")
      (node (ref "BRD1") (pin "32") (pinfunction "SCL_32") (pintype "bidirectional"))
      (node (ref "R26") (pin "1") (pinfunction "P$1_1") (pintype "passive"))
    )
    (net (code "26") (name "Net-(BRD1-SDA)") (class "Default")
      (node (ref "BRD1") (pin "31") (pinfunction "SDA_31") (pintype "bidirectional"))
      (node (ref "R25") (pin "1") (pinfunction "P$1_1") (pintype "passive"))
    )
    (net (code "27") (name "Net-(C3-P$1)") (class "Default")
      (node (ref "C3") (pin "1") (pinfunction "P$1_1") (pintype "passive"))
      (node (ref "C4") (pin "2") (pinfunction "P$2_2") (pintype "passive"))
      (node (ref "L1") (pin "1") (pinfunction "P$1_1") (pintype "bidirectional"))
      (node (ref "R1") (pin "1") (pinfunction "P$1_1") (pintype "passive"))
      (node (ref "U1") (pin "P$37") (pinfunction "ANT1_P$37") (pintype "bidirectional"))
    )
    (net (code "28") (name "Net-(C8-P$1)") (class "Default")
      (node (ref "C8") (pin "1") (pinfunction "P$1_1") (pintype "passive"))
      (node (ref "D3") (pin "K") (pinfunction "K_K") (pintype "passive"))
      (node (ref "D4") (pin "K") (pinfunction "K_K") (pintype "passive"))
      (node (ref "D5") (pin "K") (pinfunction "K_K") (pintype "passive"))
      (node (ref "U2") (pin "1") (pinfunction "IN_1") (pintype "bidirectional"))
      (node (ref "U2") (pin "3") (pinfunction "EN_3") (pintype "bidirectional"))
    )
    (net (code "29") (name "Net-(C10-P$1)") (class "Default")
      (node (ref "C10") (pin "1") (pinfunction "P$1_1") (pintype "passive"))
      (node (ref "R9") (pin "2") (pinfunction "P$2_2") (pintype "passive"))
      (node (ref "U4") (pin "2") (pinfunction "IF_NRESET_2") (pintype "bidirectional"))
    )
    (net (code "30") (name "Net-(C12-P$1)") (class "Default")
      (node (ref "C12") (pin "1") (pinfunction "P$1_1") (pintype "passive"))
      (node (ref "R7") (pin "2") (pinfunction "P$2_2") (pintype "passive"))
      (node (ref "U4") (pin "13") (pinfunction "USB_D-_13") (pintype "bidirectional"))
    )
    (net (code "31") (name "Net-(C13-P$1)") (class "Default")
      (node (ref "C13") (pin "1") (pinfunction "P$1_1") (pintype "passive"))
      (node (ref "R4") (pin "2") (pinfunction "P$2_2") (pintype "passive"))
      (node (ref "R8") (pin "2") (pinfunction "P$2_2") (pintype "passive"))
      (node (ref "U4") (pin "14") (pinfunction "USB_D+_14") (pintype "bidirectional"))
    )
    (net (code "32") (name "Net-(C14-P$1)") (class "Default")
      (node (ref "C14") (pin "1") (pinfunction "P$1_1") (pintype "passive"))
      (node (ref "Q1") (pin "P$1") (pinfunction "1_P$1") (pintype "passive"))
      (node (ref "U4") (pin "4") (pinfunction "XTALIN_4") (pintype "bidirectional"))
    )
    (net (code "33") (name "Net-(C15-P$1)") (class "Default")
      (node (ref "C15") (pin "1") (pinfunction "P$1_1") (pintype "passive"))
      (node (ref "Q1") (pin "P$3") (pinfunction "2_P$3") (pintype "passive"))
      (node (ref "U4") (pin "5") (pinfunction "XTALOUT_5") (pintype "bidirectional"))
    )
    (net (code "34") (name "Net-(C17-P$2)") (class "Default")
      (node (ref "C17") (pin "2") (pinfunction "P$2_2") (pintype "passive"))
      (node (ref "R28") (pin "1") (pinfunction "P$1_1") (pintype "passive"))
      (node (ref "U3") (pin "6") (pinfunction "VCC_6") (pintype "bidirectional"))
    )
    (net (code "35") (name "Net-(R2-P$1)") (class "Default")
      (node (ref "LED1") (pin "A") (pinfunction "A_A") (pintype "passive"))
      (node (ref "R2") (pin "1") (pinfunction "P$1_1") (pintype "passive"))
    )
    (net (code "36") (name "Net-(R3-P$1)") (class "Default")
      (node (ref "LED2") (pin "A") (pinfunction "A_A") (pintype "passive"))
      (node (ref "R3") (pin "1") (pinfunction "P$1_1") (pintype "passive"))
    )
    (net (code "37") (name "Net-(R8-P$1)") (class "Default")
      (node (ref "R8") (pin "1") (pinfunction "P$1_1") (pintype "passive"))
      (node (ref "T1") (pin "3") (pinfunction "D_3") (pintype "passive"))
    )
    (net (code "38") (name "Net-(R10-P$2)") (class "Default")
      (node (ref "R10") (pin "2") (pinfunction "P$2_2") (pintype "passive"))
      (node (ref "U4") (pin "9") (pinfunction "USB_VBUS_9") (pintype "bidirectional"))
    )
    (net (code "39") (name "Net-(R11-P$1)") (class "Default")
      (node (ref "LED3") (pin "C") (pinfunction "C_C") (pintype "passive"))
      (node (ref "R11") (pin "1") (pinfunction "P$1_1") (pintype "passive"))
    )
    (net (code "40") (name "Net-(R11-P$2)") (class "Default")
      (node (ref "R11") (pin "2") (pinfunction "P$2_2") (pintype "passive"))
      (node (ref "U4") (pin "7") (pinfunction "LED_MSD_7") (pintype "bidirectional"))
    )
    (net (code "41") (name "Net-(R12-P$1)") (class "Default")
      (node (ref "LED4") (pin "C") (pinfunction "C_C") (pintype "passive"))
      (node (ref "R12") (pin "1") (pinfunction "P$1_1") (pintype "passive"))
    )
    (net (code "42") (name "Net-(R12-P$2)") (class "Default")
      (node (ref "R12") (pin "2") (pinfunction "P$2_2") (pintype "passive"))
      (node (ref "U4") (pin "12") (pinfunction "LED_HID_12") (pintype "bidirectional"))
    )
    (net (code "43") (name "Net-(R13-P$1)") (class "Default")
      (node (ref "LED5") (pin "C") (pinfunction "C_C") (pintype "passive"))
      (node (ref "R13") (pin "1") (pinfunction "P$1_1") (pintype "passive"))
    )
    (net (code "44") (name "Net-(R13-P$2)") (class "Default")
      (node (ref "R13") (pin "2") (pinfunction "P$2_2") (pintype "passive"))
      (node (ref "U4") (pin "21") (pinfunction "LED_UART_21") (pintype "bidirectional"))
    )
    (net (code "45") (name "Net-(R17-P$2)") (class "Default")
      (node (ref "R17") (pin "2") (pinfunction "P$2_2") (pintype "passive"))
      (node (ref "SW3") (pin "6") (pinfunction "6_6") (pintype "bidirectional"))
    )
    (net (code "46") (name "Net-(R18-P$2)") (class "Default")
      (node (ref "R18") (pin "2") (pinfunction "P$2_2") (pintype "passive"))
      (node (ref "SW3") (pin "2") (pinfunction "2_2") (pintype "bidirectional"))
    )
    (net (code "47") (name "Net-(RESET-S)") (class "Default")
      (node (ref "D6") (pin "K") (pinfunction "K_K") (pintype "passive"))
      (node (ref "RESET") (pin "P$2") (pinfunction "S_P$2") (pintype "passive"))
      (node (ref "U4") (pin "1") (pinfunction "NRESET_FB_BL_1") (pintype "bidirectional"))
      (node (ref "U4") (pin "3") (pinfunction "NRESET_FB_ISP_3") (pintype "bidirectional"))
    )
    (net (code "48") (name "Net-(T1-G)") (class "Default")
      (node (ref "T1") (pin "1") (pinfunction "G_1") (pintype "passive"))
      (node (ref "U4") (pin "15") (pinfunction "USB_SCON_15") (pintype "bidirectional"))
    )
    (net (code "49") (name "P4V5_VBAT") (class "Default")
      (node (ref "CON2") (pin "1") (pinfunction "+_1") (pintype "bidirectional"))
      (node (ref "D5") (pin "A") (pinfunction "A_A") (pintype "passive"))
    )
    (net (code "50") (name "P5V-VIN") (class "Default")
      (node (ref "BRD1") (pin "8") (pinfunction "VIN_8") (pintype "bidirectional"))
      (node (ref "D4") (pin "A") (pinfunction "A_A") (pintype "passive"))
    )
    (net (code "51") (name "P5V_USB") (class "Default")
      (node (ref "C16") (pin "1") (pinfunction "P$1_1") (pintype "passive"))
      (node (ref "CON1") (pin "VBUS") (pinfunction "VBUS_VBUS") (pintype "bidirectional"))
      (node (ref "D1") (pin "A") (pinfunction "A_A") (pintype "passive"))
      (node (ref "D3") (pin "A") (pinfunction "A_A") (pintype "passive"))
    )
    (net (code "52") (name "RFU1") (class "Default")
      (node (ref "U1") (pin "P$2") (pinfunction "RFU1_P$2") (pintype "bidirectional"))
    )
    (net (code "53") (name "RFU2") (class "Default")
      (node (ref "R6") (pin "2") (pinfunction "P$2_2") (pintype "passive"))
      (node (ref "U1") (pin "P$6") (pinfunction "RFU2_P$6") (pintype "bidirectional"))
    )
    (net (code "54") (name "RFU3") (class "Default")
      (node (ref "U1") (pin "P$7") (pinfunction "RFU3_P$7") (pintype "bidirectional"))
    )
    (net (code "55") (name "RFU4") (class "Default")
      (node (ref "U1") (pin "P$8") (pinfunction "RFU4_P$8") (pintype "bidirectional"))
    )
    (net (code "56") (name "RFU5") (class "Default")
      (node (ref "U1") (pin "P$18") (pinfunction "RFU5_P$18") (pintype "bidirectional"))
    )
    (net (code "57") (name "RFU6") (class "Default")
      (node (ref "U1") (pin "P$19") (pinfunction "RFU6_P$19") (pintype "bidirectional"))
    )
    (net (code "58") (name "RFU7") (class "Default")
      (node (ref "U1") (pin "P$21") (pinfunction "RFU7_P$21") (pintype "bidirectional"))
    )
    (net (code "59") (name "RFU8") (class "Default")
      (node (ref "U1") (pin "P$22") (pinfunction "RFU8_P$22") (pintype "bidirectional"))
    )
    (net (code "60") (name "SPI_MISO") (class "Default")
      (node (ref "R23") (pin "2") (pinfunction "P$2_2") (pintype "passive"))
      (node (ref "U1") (pin "P$12") (pinfunction "SPI_MISO_P$12") (pintype "bidirectional"))
      (node (ref "U3") (pin "8") (pinfunction "SO_8") (pintype "bidirectional"))
    )
    (net (code "61") (name "SPI_MOSI") (class "Default")
      (node (ref "R22") (pin "2") (pinfunction "P$2_2") (pintype "passive"))
      (node (ref "U1") (pin "P$11") (pinfunction "SPI_MOSI_P$11") (pintype "bidirectional"))
      (node (ref "U3") (pin "1") (pinfunction "SI_1") (pintype "bidirectional"))
    )
    (net (code "62") (name "SPI_NSS") (class "Default")
      (node (ref "R21") (pin "2") (pinfunction "P$2_2") (pintype "passive"))
      (node (ref "U1") (pin "P$9") (pinfunction "SPI_NSS_P$9") (pintype "bidirectional"))
      (node (ref "U3") (pin "4") (pinfunction "~{CS}_4") (pintype "bidirectional"))
    )
    (net (code "63") (name "SPI_SCK") (class "Default")
      (node (ref "R24") (pin "2") (pinfunction "P$2_2") (pintype "passive"))
      (node (ref "U1") (pin "P$10") (pinfunction "SPI_SCK_P$10") (pintype "bidirectional"))
      (node (ref "U3") (pin "2") (pinfunction "SCK_2") (pintype "bidirectional"))
    )
    (net (code "64") (name "TGT_NRESET") (class "Default")
      (node (ref "BRD1") (pin "3") (pinfunction "NRESET_3") (pintype "bidirectional"))
      (node (ref "D6") (pin "A") (pinfunction "A_A") (pintype "passive"))
      (node (ref "U1") (pin "P$33") (pinfunction "NRESET_P$33") (pintype "bidirectional"))
      (node (ref "U4") (pin "8") (pinfunction "TGT_NRESET_8") (pintype "bidirectional"))
    )
    (net (code "65") (name "TGT_RX") (class "Default")
      (node (ref "U1") (pin "P$16") (pinfunction "UART0_RX_P$16") (pintype "bidirectional"))
      (node (ref "U4") (pin "32") (pinfunction "TGT_RX_32") (pintype "bidirectional"))
    )
    (net (code "66") (name "TGT_SWCLK") (class "Default")
      (node (ref "U1") (pin "P$29") (pinfunction "SWCLK_P$29") (pintype "bidirectional"))
      (node (ref "U4") (pin "16") (pinfunction "TGT_SWCLK_16") (pintype "bidirectional"))
    )
    (net (code "67") (name "TGT_SWDIO") (class "Default")
      (node (ref "U1") (pin "P$30") (pinfunction "SWDIO_P$30") (pintype "bidirectional"))
      (node (ref "U4") (pin "17") (pinfunction "TGT_SWDIO_17") (pintype "bidirectional"))
    )
    (net (code "68") (name "TGT_TX") (class "Default")
      (node (ref "U1") (pin "P$15") (pinfunction "UART0_TX_P$15") (pintype "bidirectional"))
      (node (ref "U4") (pin "31") (pinfunction "TGT_TX_31") (pintype "bidirectional"))
    )
    (net (code "69") (name "UART1_CTS") (class "Default")
      (node (ref "R19") (pin "2") (pinfunction "P$2_2") (pintype "passive"))
      (node (ref "U1") (pin "P$32") (pinfunction "UART1_CTS_P$32") (pintype "bidirectional"))
    )
    (net (code "70") (name "UART1_RTS") (class "Default")
      (node (ref "R20") (pin "2") (pinfunction "P$2_2") (pintype "passive"))
      (node (ref "U1") (pin "P$31") (pinfunction "UART1_RTS_P$31") (pintype "bidirectional"))
    )
    (net (code "71") (name "UART1_RX") (class "Default")
      (node (ref "SW3") (pin "3") (pinfunction "3_3") (pintype "bidirectional"))
      (node (ref "SW3") (pin "5") (pinfunction "5_5") (pintype "bidirectional"))
      (node (ref "U1") (pin "P$14") (pinfunction "UART1_RX_P$14") (pintype "bidirectional"))
    )
    (net (code "72") (name "UART1_TX") (class "Default")
      (node (ref "SW3") (pin "1") (pinfunction "1_1") (pintype "bidirectional"))
      (node (ref "SW3") (pin "7") (pinfunction "7_7") (pintype "bidirectional"))
      (node (ref "U1") (pin "P$13") (pinfunction "UART1_TX_P$13") (pintype "bidirectional"))
    )
    (net (code "73") (name "USB_D+") (class "Default")
      (node (ref "CON1") (pin "D+") (pinfunction "D+_D+") (pintype "bidirectional"))
      (node (ref "R4") (pin "1") (pinfunction "P$1_1") (pintype "passive"))
    )
    (net (code "74") (name "USB_D-") (class "Default")
      (node (ref "CON1") (pin "D-") (pinfunction "D-_D-") (pintype "bidirectional"))
      (node (ref "R7") (pin "1") (pinfunction "P$1_1") (pintype "passive"))
    )
    (net (code "75") (name "WAKE") (class "Default")
      (node (ref "R14") (pin "1") (pinfunction "P$1_1") (pintype "passive"))
      (node (ref "U1") (pin "P$34") (pinfunction "WAKE_P$34") (pintype "bidirectional"))
    )
    (net (code "76") (name "unconnected-(ANT1-2-PadP$2)") (class "Default")
      (node (ref "ANT1") (pin "P$2") (pinfunction "2_P$2") (pintype "passive"))
    )
    (net (code "77") (name "unconnected-(BRD1-A3-Pad12)") (class "Default")
      (node (ref "BRD1") (pin "12") (pinfunction "A3_12") (pintype "bidirectional"))
    )
    (net (code "78") (name "unconnected-(BRD1-A4-Pad13)") (class "Default")
      (node (ref "BRD1") (pin "13") (pinfunction "A4_13") (pintype "bidirectional"))
    )
    (net (code "79") (name "unconnected-(BRD1-A5-Pad14)") (class "Default")
      (node (ref "BRD1") (pin "14") (pinfunction "A5_14") (pintype "bidirectional"))
    )
    (net (code "80") (name "unconnected-(BRD1-AREF-Pad30)") (class "Default")
      (node (ref "BRD1") (pin "30") (pinfunction "AREF_30") (pintype "bidirectional"))
    )
    (net (code "81") (name "unconnected-(BRD1-D4-Pad19)") (class "Default")
      (node (ref "BRD1") (pin "19") (pinfunction "D4_19") (pintype "bidirectional"))
    )
    (net (code "82") (name "unconnected-(BRD1-D5-Pad20)") (class "Default")
      (node (ref "BRD1") (pin "20") (pinfunction "D5_20") (pintype "bidirectional"))
    )
    (net (code "83") (name "unconnected-(BRD1-D6-Pad21)") (class "Default")
      (node (ref "BRD1") (pin "21") (pinfunction "D6_21") (pintype "bidirectional"))
    )
    (net (code "84") (name "unconnected-(BRD1-D7-Pad22)") (class "Default")
      (node (ref "BRD1") (pin "22") (pinfunction "D7_22") (pintype "bidirectional"))
    )
    (net (code "85") (name "unconnected-(BRD1-D8-Pad23)") (class "Default")
      (node (ref "BRD1") (pin "23") (pinfunction "D8_23") (pintype "bidirectional"))
    )
    (net (code "86") (name "unconnected-(BRD1-D9-Pad24)") (class "Default")
      (node (ref "BRD1") (pin "24") (pinfunction "D9_24") (pintype "bidirectional"))
    )
    (net (code "87") (name "unconnected-(BRD1-NC-Pad1)") (class "Default")
      (node (ref "BRD1") (pin "1") (pinfunction "NC_1") (pintype "bidirectional"))
    )
    (net (code "88") (name "unconnected-(U1-ANT2-PadP$47)") (class "Default")
      (node (ref "U1") (pin "P$47") (pinfunction "ANT2_P$47") (pintype "bidirectional"))
    )
    (net (code "89") (name "unconnected-(U2-NC-Pad4)") (class "Default")
      (node (ref "U2") (pin "4") (pinfunction "NC_4") (pintype "bidirectional"))
    )
    (net (code "90") (name "unconnected-(U4-NC2-Pad10)") (class "Default")
      (node (ref "U4") (pin "10") (pinfunction "NC2_10") (pintype "bidirectional"))
    )
    (net (code "91") (name "unconnected-(U4-NC3-Pad11)") (class "Default")
      (node (ref "U4") (pin "11") (pinfunction "NC3_11") (pintype "bidirectional"))
    )
    (net (code "92") (name "unconnected-(U4-NC4-Pad19)") (class "Default")
      (node (ref "U4") (pin "19") (pinfunction "NC4_19") (pintype "bidirectional"))
    )
    (net (code "93") (name "unconnected-(U4-NC5-Pad20)") (class "Default")
      (node (ref "U4") (pin "20") (pinfunction "NC5_20") (pintype "bidirectional"))
    )
    (net (code "94") (name "unconnected-(U4-NC6-Pad22)") (class "Default")
      (node (ref "U4") (pin "22") (pinfunction "NC6_22") (pintype "bidirectional"))
    )
    (net (code "95") (name "unconnected-(U4-NC7-Pad23)") (class "Default")
      (node (ref "U4") (pin "23") (pinfunction "NC7_23") (pintype "bidirectional"))
    )
    (net (code "96") (name "unconnected-(U4-NC8-Pad24)") (class "Default")
      (node (ref "U4") (pin "24") (pinfunction "NC8_24") (pintype "bidirectional"))
    )
    (net (code "97") (name "unconnected-(U4-NC9-Pad25)") (class "Default")
      (node (ref "U4") (pin "25") (pinfunction "NC9_25") (pintype "bidirectional"))
    )
    (net (code "98") (name "unconnected-(U4-NC10-Pad28)") (class "Default")
      (node (ref "U4") (pin "28") (pinfunction "NC10_28") (pintype "bidirectional"))
    )
    (net (code "99") (name "unconnected-(U4-NC11-Pad30)") (class "Default")
      (node (ref "U4") (pin "30") (pinfunction "NC11_30") (pintype "bidirectional"))
    )
    (net (code "100") (name "unconnected-(U4-SLEEP_NREQ-Pad27)") (class "Default")
      (node (ref "U4") (pin "27") (pinfunction "SLEEP_NREQ_27") (pintype "bidirectional"))
    )
    (net (code "101") (name "unconnected-(U4-TGT_SWO-Pad18)") (class "Default")
      (node (ref "U4") (pin "18") (pinfunction "TGT_SWO_18") (pintype "bidirectional"))
    )
    (net (code "102") (name "unconnected-(U4-WAKE_NREQ-Pad26)") (class "Default")
      (node (ref "U4") (pin "26") (pinfunction "WAKE_NREQ_26") (pintype "bidirectional"))
    )
  )
)
